# GarageDoorOpener.net
KiCad netlist of a schematic drawn in EAGLE
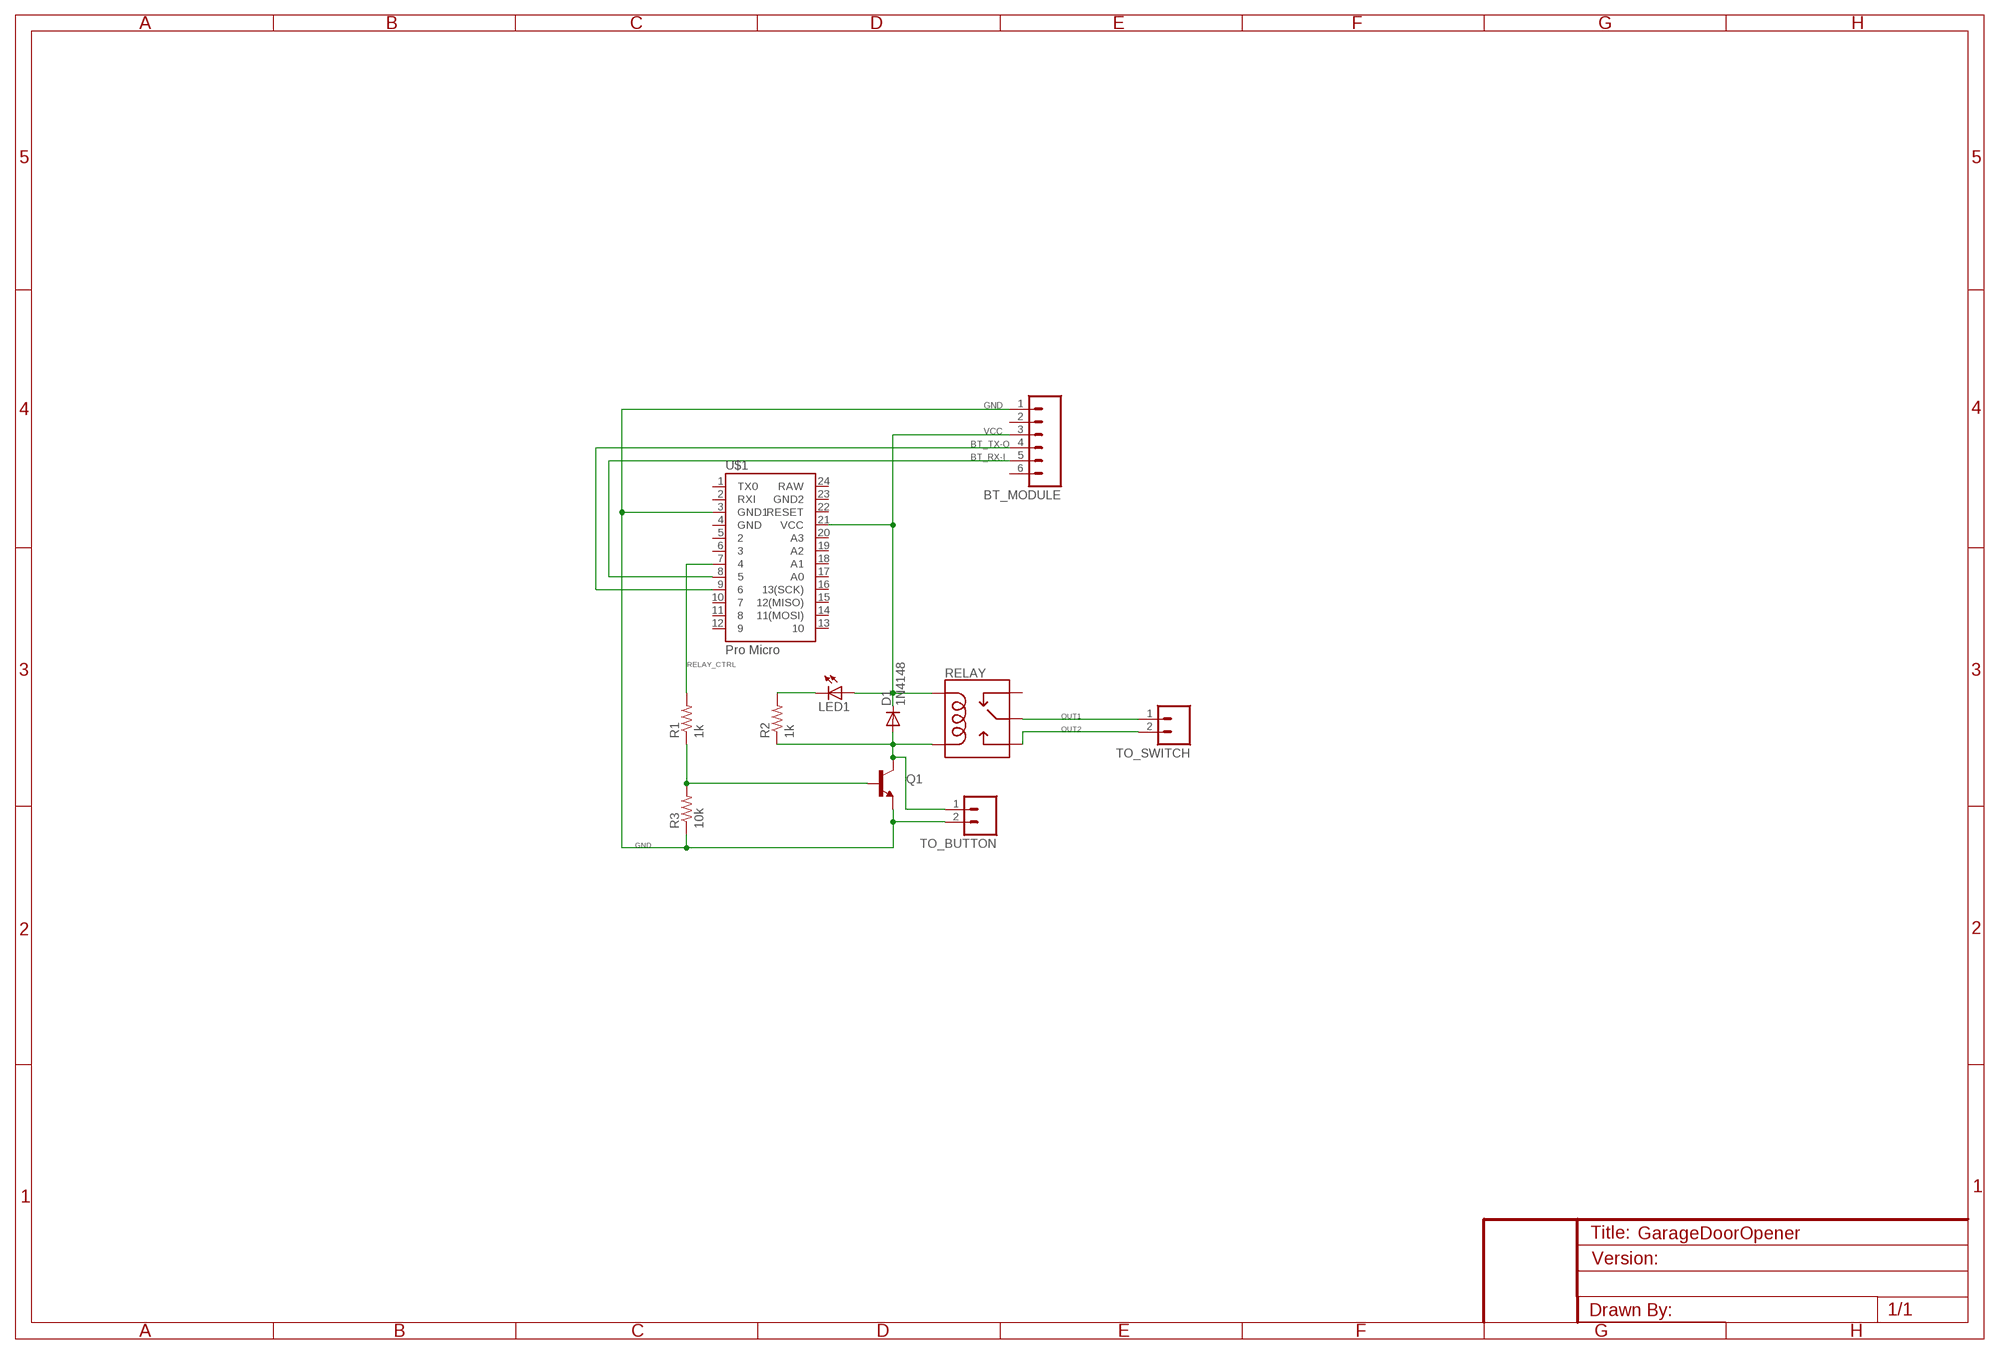
[diagram p0: schematic, sheet 1]

(export (version "E")
  (design (tool "Eeschema 10.0.6"))
  (components
    (comp (ref "BT_MODULE")
      (value "M06LOCK")
      (footprint "eagle-import:1X06_LOCK")
      (libsource (lib "eagle-import") (part "M06LOCK"))
    )
    (comp (ref "D1")
      (value "1N4148")
      (footprint "eagle-import:DIODE-1N4148")
      (libsource (lib "eagle-import") (part "DIODE1N4148"))
    )
    (comp (ref "LED1")
      (value "LED3MM")
      (footprint "eagle-import:LED3MM")
      (libsource (lib "eagle-import") (part "LED3MM"))
    )
    (comp (ref "Q1")
      (value "TRANSISTOR_NPNTO-92-AMMO")
      (footprint "eagle-import:TO-92-AMMO")
      (libsource (lib "eagle-import") (part "TRANSISTOR_NPNTO-92-AMMO"))
    )
    (comp (ref "R1")
      (value "1k")
      (footprint "eagle-import:AXIAL-0.3")
      (libsource (lib "eagle-import") (part "RESISTORAXIAL-0.3"))
    )
    (comp (ref "R2")
      (value "1k")
      (footprint "eagle-import:AXIAL-0.3")
      (libsource (lib "eagle-import") (part "RESISTORAXIAL-0.3"))
    )
    (comp (ref "R3")
      (value "10k")
      (footprint "eagle-import:AXIAL-0.3")
      (libsource (lib "eagle-import") (part "RESISTORAXIAL-0.3"))
    )
    (comp (ref "RELAY")
      (value "RELAYPTH4")
      (footprint "eagle-import:RELAY-JZC")
      (libsource (lib "eagle-import") (part "RELAYPTH4"))
    )
    (comp (ref "TO_BUTTON")
      (value "M02LOCK")
      (footprint "eagle-import:1X02_LOCK")
      (libsource (lib "eagle-import") (part "M02LOCK"))
    )
    (comp (ref "TO_SWITCH")
      (value "M02-JST-2-PTH-NO_SILK")
      (footprint "eagle-import:JST-2-PTH-NS")
      (libsource (lib "eagle-import") (part "M02-JST-2-PTH-NO_SILK"))
    )
    (comp (ref "U$1")
      (value "Pro Micro")
      (footprint "eagle-import:ARDUINO_PRO_MICRO")
      (libsource (lib "eagle-import") (part "ARDUINO_PRO_MICRO"))
    )
  )
  (nets
    (net (code "1") (name "/BT_RX-I") (class "Default")
      (node (ref "BT_MODULE") (pin "5") (pinfunction "5_5") (pintype "passive"))
      (node (ref "U$1") (pin "8") (pinfunction "5_8") (pintype "bidirectional"))
    )
    (net (code "2") (name "/BT_TX-O") (class "Default")
      (node (ref "BT_MODULE") (pin "4") (pinfunction "4_4") (pintype "passive"))
      (node (ref "U$1") (pin "9") (pinfunction "6_9") (pintype "bidirectional"))
    )
    (net (code "3") (name "/GND") (class "Default")
      (node (ref "BT_MODULE") (pin "1") (pinfunction "1_1") (pintype "passive"))
      (node (ref "Q1") (pin "1") (pinfunction "E_1") (pintype "passive"))
      (node (ref "R3") (pin "P$1") (pinfunction "1_P$1") (pintype "passive"))
      (node (ref "TO_BUTTON") (pin "2") (pinfunction "2_2") (pintype "passive"))
      (node (ref "U$1") (pin "3") (pinfunction "GND1_3") (pintype "bidirectional"))
    )
    (net (code "4") (name "/OUT1") (class "Default")
      (node (ref "RELAY") (pin "4") (pinfunction "MAIN_4") (pintype "bidirectional"))
      (node (ref "TO_SWITCH") (pin "1") (pinfunction "1_1") (pintype "passive"))
    )
    (net (code "5") (name "/OUT2") (class "Default")
      (node (ref "RELAY") (pin "3") (pinfunction "NO_3") (pintype "bidirectional"))
      (node (ref "TO_SWITCH") (pin "2") (pinfunction "2_2") (pintype "passive"))
    )
    (net (code "6") (name "/RELAY_CTRL") (class "Default")
      (node (ref "R1") (pin "P$2") (pinfunction "2_P$2") (pintype "passive"))
      (node (ref "U$1") (pin "7") (pinfunction "4_7") (pintype "bidirectional"))
    )
    (net (code "7") (name "/VCC") (class "Default")
      (node (ref "BT_MODULE") (pin "3") (pinfunction "3_3") (pintype "passive"))
      (node (ref "D1") (pin "C") (pinfunction "C_C") (pintype "passive"))
      (node (ref "LED1") (pin "A") (pinfunction "A_A") (pintype "passive"))
      (node (ref "RELAY") (pin "5") (pinfunction "COIL1_5") (pintype "bidirectional"))
      (node (ref "U$1") (pin "21") (pinfunction "VCC_21") (pintype "bidirectional"))
    )
    (net (code "8") (name "Net-(LED1-C)") (class "Default")
      (node (ref "LED1") (pin "K") (pinfunction "C_K") (pintype "passive"))
      (node (ref "R2") (pin "P$2") (pinfunction "2_P$2") (pintype "passive"))
    )
    (net (code "9") (name "Net-(Q1-B)") (class "Default")
      (node (ref "Q1") (pin "2") (pinfunction "B_2") (pintype "passive"))
      (node (ref "R1") (pin "P$1") (pinfunction "1_P$1") (pintype "passive"))
      (node (ref "R3") (pin "P$2") (pinfunction "2_P$2") (pintype "passive"))
    )
    (net (code "10") (name "Net-(Q1-C)") (class "Default")
      (node (ref "D1") (pin "A") (pinfunction "A_A") (pintype "passive"))
      (node (ref "Q1") (pin "3") (pinfunction "C_3") (pintype "passive"))
      (node (ref "R2") (pin "P$1") (pinfunction "1_P$1") (pintype "passive"))
      (node (ref "RELAY") (pin "1") (pinfunction "COIL2_1") (pintype "bidirectional"))
      (node (ref "TO_BUTTON") (pin "1") (pinfunction "1_1") (pintype "passive"))
    )
    (net (code "11") (name "unconnected-(BT_MODULE-Pad2)") (class "Default")
      (node (ref "BT_MODULE") (pin "2") (pinfunction "2_2") (pintype "passive"))
    )
    (net (code "12") (name "unconnected-(BT_MODULE-Pad6)") (class "Default")
      (node (ref "BT_MODULE") (pin "6") (pinfunction "6_6") (pintype "passive"))
    )
    (net (code "13") (name "unconnected-(RELAY-NC-Pad2)") (class "Default")
      (node (ref "RELAY") (pin "2") (pinfunction "NC_2") (pintype "bidirectional"))
    )
    (net (code "14") (name "unconnected-(U$1-2-Pad5)") (class "Default")
      (node (ref "U$1") (pin "5") (pinfunction "2_5") (pintype "bidirectional"))
    )
    (net (code "15") (name "unconnected-(U$1-3-Pad6)") (class "Default")
      (node (ref "U$1") (pin "6") (pinfunction "3_6") (pintype "bidirectional"))
    )
    (net (code "16") (name "unconnected-(U$1-7-Pad10)") (class "Default")
      (node (ref "U$1") (pin "10") (pinfunction "7_10") (pintype "bidirectional"))
    )
    (net (code "17") (name "unconnected-(U$1-8-Pad11)") (class "Default")
      (node (ref "U$1") (pin "11") (pinfunction "8_11") (pintype "bidirectional"))
    )
    (net (code "18") (name "unconnected-(U$1-9-Pad12)") (class "Default")
      (node (ref "U$1") (pin "12") (pinfunction "9_12") (pintype "bidirectional"))
    )
    (net (code "19") (name "unconnected-(U$1-10-Pad13)") (class "Default")
      (node (ref "U$1") (pin "13") (pinfunction "10_13") (pintype "bidirectional"))
    )
    (net (code "20") (name "unconnected-(U$1-11(MOSI)-Pad14)") (class "Default")
      (node (ref "U$1") (pin "14") (pinfunction "11(MOSI)_14") (pintype "bidirectional"))
    )
    (net (code "21") (name "unconnected-(U$1-12(MISO)-Pad15)") (class "Default")
      (node (ref "U$1") (pin "15") (pinfunction "12(MISO)_15") (pintype "bidirectional"))
    )
    (net (code "22") (name "unconnected-(U$1-13(SCK)-Pad16)") (class "Default")
      (node (ref "U$1") (pin "16") (pinfunction "13(SCK)_16") (pintype "bidirectional"))
    )
    (net (code "23") (name "unconnected-(U$1-A0-Pad17)") (class "Default")
      (node (ref "U$1") (pin "17") (pinfunction "A0_17") (pintype "bidirectional"))
    )
    (net (code "24") (name "unconnected-(U$1-A1-Pad18)") (class "Default")
      (node (ref "U$1") (pin "18") (pinfunction "A1_18") (pintype "bidirectional"))
    )
    (net (code "25") (name "unconnected-(U$1-A2-Pad19)") (class "Default")
      (node (ref "U$1") (pin "19") (pinfunction "A2_19") (pintype "bidirectional"))
    )
    (net (code "26") (name "unconnected-(U$1-A3-Pad20)") (class "Default")
      (node (ref "U$1") (pin "20") (pinfunction "A3_20") (pintype "bidirectional"))
    )
    (net (code "27") (name "unconnected-(U$1-GND-Pad4)") (class "Default")
      (node (ref "U$1") (pin "4") (pinfunction "GND_4") (pintype "bidirectional"))
    )
    (net (code "28") (name "unconnected-(U$1-GND2-Pad23)") (class "Default")
      (node (ref "U$1") (pin "23") (pinfunction "GND2_23") (pintype "bidirectional"))
    )
    (net (code "29") (name "unconnected-(U$1-RAW-Pad24)") (class "Default")
      (node (ref "U$1") (pin "24") (pinfunction "RAW_24") (pintype "bidirectional"))
    )
    (net (code "30") (name "unconnected-(U$1-RESET-Pad22)") (class "Default")
      (node (ref "U$1") (pin "22") (pinfunction "RESET_22") (pintype "bidirectional"))
    )
    (net (code "31") (name "unconnected-(U$1-RXI-Pad2)") (class "Default")
      (node (ref "U$1") (pin "2") (pinfunction "RXI_2") (pintype "bidirectional"))
    )
    (net (code "32") (name "unconnected-(U$1-TX0-Pad1)") (class "Default")
      (node (ref "U$1") (pin "1") (pinfunction "TX0_1") (pintype "bidirectional"))
    )
  )
)
